# MotorController.net
KiCad netlist of a schematic drawn in EAGLE
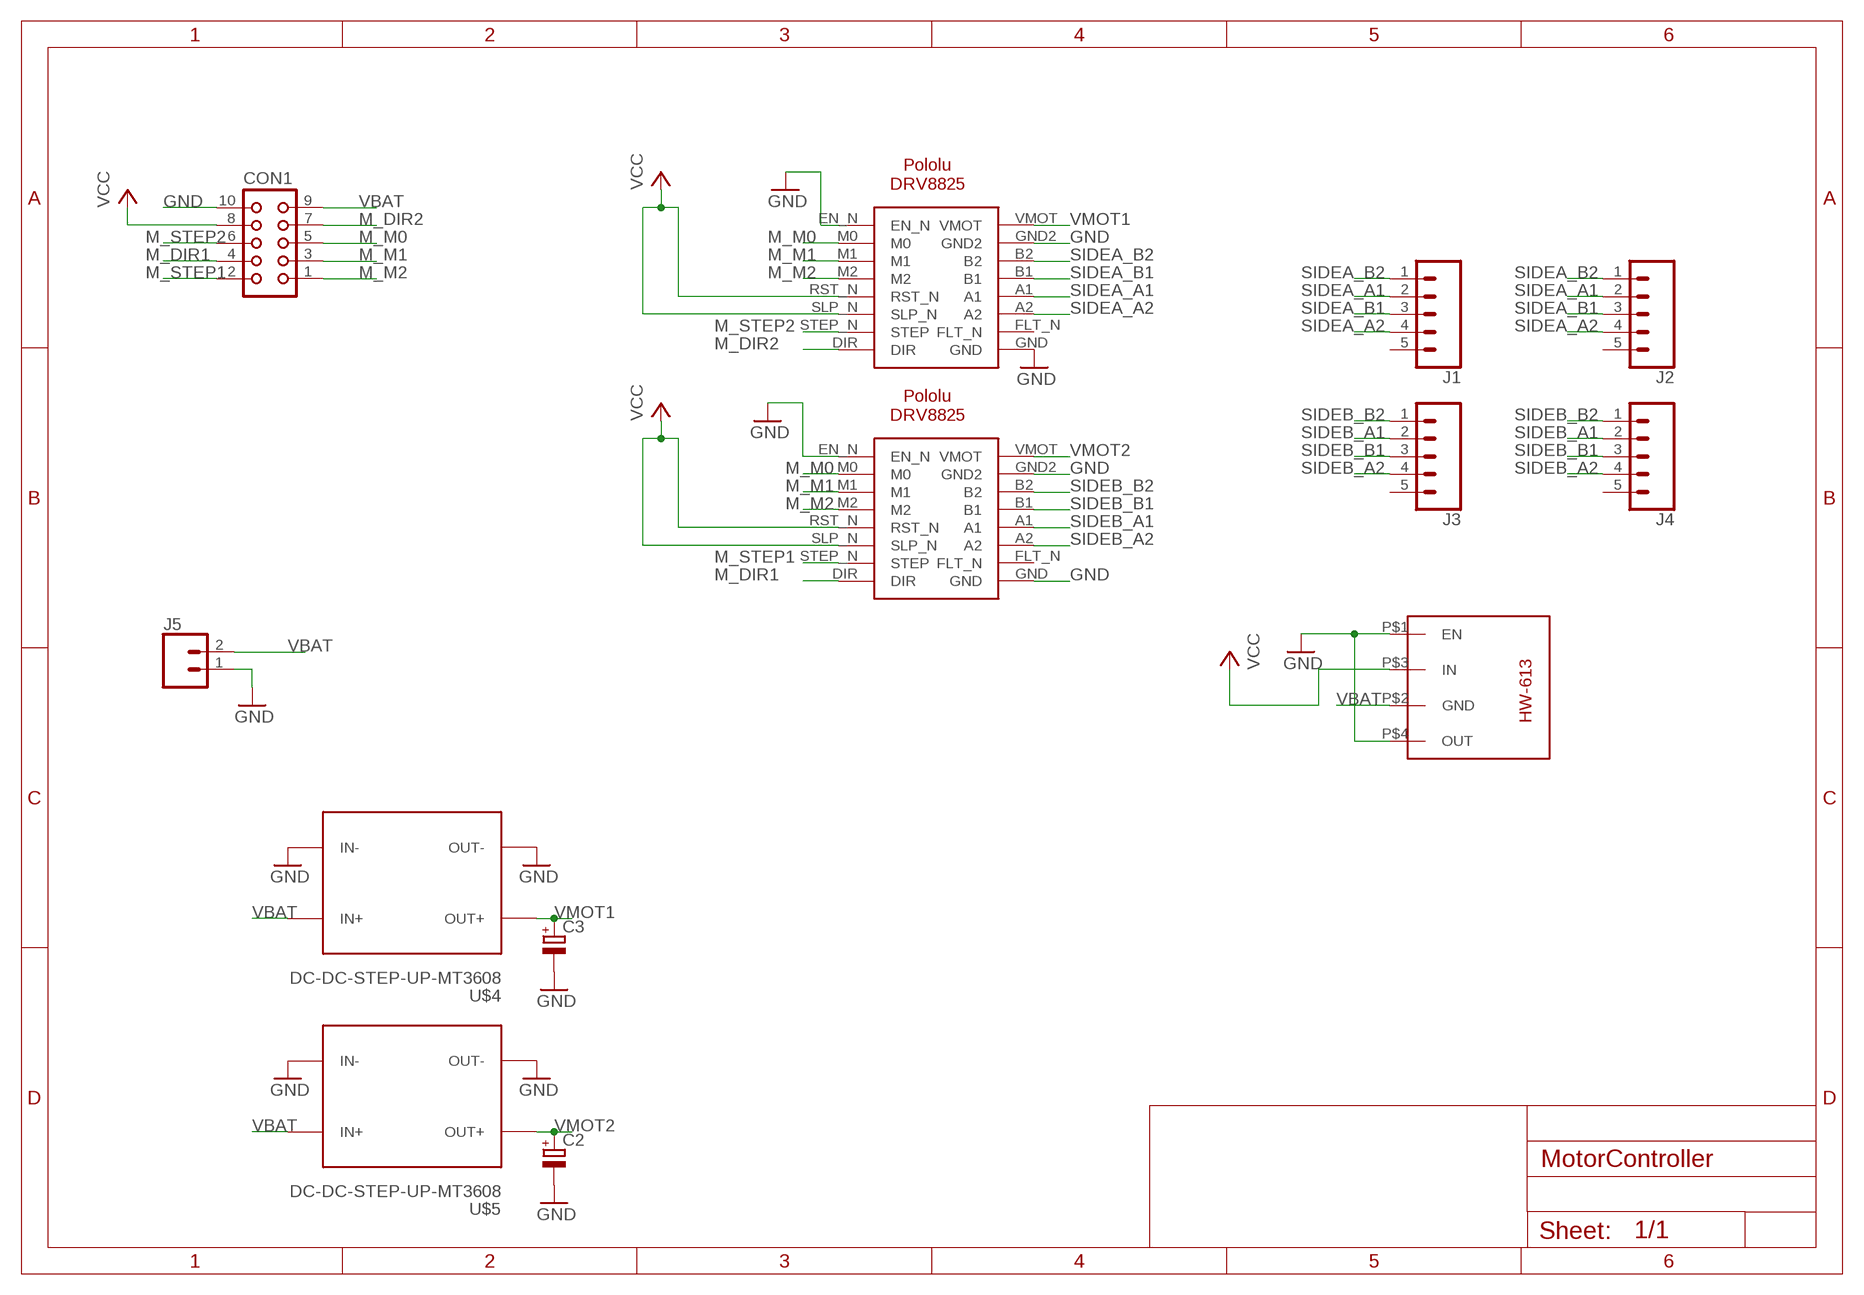
[diagram p0: schematic, sheet 1]

(export (version "E")
  (design (tool "Eeschema 10.0.6"))
  (components
    (comp (ref "C2")
      (value "CPOL-EUE3.5-10")
      (footprint "eagle-import:E3,5-10")
      (libsource (lib "eagle-import") (part "CPOL-EUE3.5-10"))
    )
    (comp (ref "C3")
      (value "CPOL-EUE3.5-10")
      (footprint "eagle-import:E3,5-10")
      (libsource (lib "eagle-import") (part "CPOL-EUE3.5-10"))
    )
    (comp (ref "CON1")
      (value "CON10")
      (footprint "eagle-import:CON10")
      (libsource (lib "eagle-import") (part "CON10"))
    )
    (comp (ref "J1")
      (value "CONN_05")
      (footprint "eagle-import:1X05")
      (libsource (lib "eagle-import") (part "CONN_05"))
    )
    (comp (ref "J2")
      (value "CONN_05")
      (footprint "eagle-import:1X05")
      (libsource (lib "eagle-import") (part "CONN_05"))
    )
    (comp (ref "J3")
      (value "CONN_05")
      (footprint "eagle-import:1X05")
      (libsource (lib "eagle-import") (part "CONN_05"))
    )
    (comp (ref "J4")
      (value "CONN_05")
      (footprint "eagle-import:1X05")
      (libsource (lib "eagle-import") (part "CONN_05"))
    )
    (comp (ref "J5")
      (value "CONN_025MM")
      (footprint "eagle-import:SCREWTERMINAL-5MM-2")
      (libsource (lib "eagle-import") (part "CONN_025MM"))
    )
    (comp (ref "U$1")
      (value "POLOLU-DRV8825")
      (footprint "eagle-import:POLOLU-DRV8825")
      (libsource (lib "eagle-import") (part "POLOLU-DRV8825"))
    )
    (comp (ref "U$2")
      (value "POLOLU-DRV8825")
      (footprint "eagle-import:POLOLU-DRV8825")
      (libsource (lib "eagle-import") (part "POLOLU-DRV8825"))
    )
    (comp (ref "U$4")
      (value "DC-DC-STEP-UP-MT3608")
      (footprint "eagle-import:DC-DC-STEP-UP-MT3608")
      (libsource (lib "eagle-import") (part "DC-DC-STEP-UP-MT3608"))
    )
    (comp (ref "U$5")
      (value "DC-DC-STEP-UP-MT3608")
      (footprint "eagle-import:DC-DC-STEP-UP-MT3608")
      (libsource (lib "eagle-import") (part "DC-DC-STEP-UP-MT3608"))
    )
    (comp (ref "U$6")
      (value "HW-613")
      (footprint "eagle-import:HW-613")
      (libsource (lib "eagle-import") (part "HW-613"))
    )
  )
  (nets
    (net (code "1") (name "/M_DIR1") (class "Default")
      (node (ref "CON1") (pin "4") (pinfunction "4_4") (pintype "passive"))
      (node (ref "U$2") (pin "DIR") (pinfunction "DIR_DIR") (pintype "bidirectional"))
    )
    (net (code "2") (name "/M_DIR2") (class "Default")
      (node (ref "CON1") (pin "7") (pinfunction "7_7") (pintype "passive"))
      (node (ref "U$1") (pin "DIR") (pinfunction "DIR_DIR") (pintype "bidirectional"))
    )
    (net (code "3") (name "/M_M0") (class "Default")
      (node (ref "CON1") (pin "5") (pinfunction "5_5") (pintype "passive"))
      (node (ref "U$1") (pin "M0") (pinfunction "M0_M0") (pintype "bidirectional"))
      (node (ref "U$2") (pin "M0") (pinfunction "M0_M0") (pintype "bidirectional"))
    )
    (net (code "4") (name "/M_M1") (class "Default")
      (node (ref "CON1") (pin "3") (pinfunction "3_3") (pintype "passive"))
      (node (ref "U$1") (pin "M1") (pinfunction "M1_M1") (pintype "bidirectional"))
      (node (ref "U$2") (pin "M1") (pinfunction "M1_M1") (pintype "bidirectional"))
    )
    (net (code "5") (name "/M_M2") (class "Default")
      (node (ref "CON1") (pin "1") (pinfunction "1_1") (pintype "passive"))
      (node (ref "U$1") (pin "M2") (pinfunction "M2_M2") (pintype "bidirectional"))
      (node (ref "U$2") (pin "M2") (pinfunction "M2_M2") (pintype "bidirectional"))
    )
    (net (code "6") (name "/M_STEP1") (class "Default")
      (node (ref "CON1") (pin "2") (pinfunction "2_2") (pintype "passive"))
      (node (ref "U$2") (pin "STEP_N") (pinfunction "STEP_STEP_N") (pintype "bidirectional"))
    )
    (net (code "7") (name "/M_STEP2") (class "Default")
      (node (ref "CON1") (pin "6") (pinfunction "6_6") (pintype "passive"))
      (node (ref "U$1") (pin "STEP_N") (pinfunction "STEP_STEP_N") (pintype "bidirectional"))
    )
    (net (code "8") (name "/SIDEA_A1") (class "Default")
      (node (ref "J1") (pin "2") (pinfunction "2_2") (pintype "passive"))
      (node (ref "J2") (pin "2") (pinfunction "2_2") (pintype "passive"))
      (node (ref "U$1") (pin "A1") (pinfunction "A1_A1") (pintype "bidirectional"))
    )
    (net (code "9") (name "/SIDEA_A2") (class "Default")
      (node (ref "J1") (pin "4") (pinfunction "4_4") (pintype "passive"))
      (node (ref "J2") (pin "4") (pinfunction "4_4") (pintype "passive"))
      (node (ref "U$1") (pin "A2") (pinfunction "A2_A2") (pintype "bidirectional"))
    )
    (net (code "10") (name "/SIDEA_B1") (class "Default")
      (node (ref "J1") (pin "3") (pinfunction "3_3") (pintype "passive"))
      (node (ref "J2") (pin "3") (pinfunction "3_3") (pintype "passive"))
      (node (ref "U$1") (pin "B1") (pinfunction "B1_B1") (pintype "bidirectional"))
    )
    (net (code "11") (name "/SIDEA_B2") (class "Default")
      (node (ref "J1") (pin "1") (pinfunction "1_1") (pintype "passive"))
      (node (ref "J2") (pin "1") (pinfunction "1_1") (pintype "passive"))
      (node (ref "U$1") (pin "B2") (pinfunction "B2_B2") (pintype "bidirectional"))
    )
    (net (code "12") (name "/SIDEB_A1") (class "Default")
      (node (ref "J3") (pin "2") (pinfunction "2_2") (pintype "passive"))
      (node (ref "J4") (pin "2") (pinfunction "2_2") (pintype "passive"))
      (node (ref "U$2") (pin "A1") (pinfunction "A1_A1") (pintype "bidirectional"))
    )
    (net (code "13") (name "/SIDEB_A2") (class "Default")
      (node (ref "J3") (pin "4") (pinfunction "4_4") (pintype "passive"))
      (node (ref "J4") (pin "4") (pinfunction "4_4") (pintype "passive"))
      (node (ref "U$2") (pin "A2") (pinfunction "A2_A2") (pintype "bidirectional"))
    )
    (net (code "14") (name "/SIDEB_B1") (class "Default")
      (node (ref "J3") (pin "3") (pinfunction "3_3") (pintype "passive"))
      (node (ref "J4") (pin "3") (pinfunction "3_3") (pintype "passive"))
      (node (ref "U$2") (pin "B1") (pinfunction "B1_B1") (pintype "bidirectional"))
    )
    (net (code "15") (name "/SIDEB_B2") (class "Default")
      (node (ref "J3") (pin "1") (pinfunction "1_1") (pintype "passive"))
      (node (ref "J4") (pin "1") (pinfunction "1_1") (pintype "passive"))
      (node (ref "U$2") (pin "B2") (pinfunction "B2_B2") (pintype "bidirectional"))
    )
    (net (code "16") (name "/VBAT") (class "Default")
      (node (ref "CON1") (pin "9") (pinfunction "9_9") (pintype "passive"))
      (node (ref "J5") (pin "2") (pinfunction "2_2") (pintype "passive"))
      (node (ref "U$4") (pin "IN+") (pinfunction "IN+_IN+") (pintype "bidirectional"))
      (node (ref "U$5") (pin "IN+") (pinfunction "IN+_IN+") (pintype "bidirectional"))
      (node (ref "U$6") (pin "P$2") (pinfunction "GND_P$2") (pintype "bidirectional"))
    )
    (net (code "17") (name "/VMOT1") (class "Default")
      (node (ref "C3") (pin "+") (pinfunction "+_+") (pintype "passive"))
      (node (ref "U$1") (pin "VMOT") (pinfunction "VMOT_VMOT") (pintype "bidirectional"))
      (node (ref "U$4") (pin "OUT+") (pinfunction "OUT+_OUT+") (pintype "bidirectional"))
    )
    (net (code "18") (name "/VMOT2") (class "Default")
      (node (ref "C2") (pin "+") (pinfunction "+_+") (pintype "passive"))
      (node (ref "U$2") (pin "VMOT") (pinfunction "VMOT_VMOT") (pintype "bidirectional"))
      (node (ref "U$5") (pin "OUT+") (pinfunction "OUT+_OUT+") (pintype "bidirectional"))
    )
    (net (code "19") (name "GND") (class "Default")
      (node (ref "C2") (pin "-") (pinfunction "-_-") (pintype "passive"))
      (node (ref "C3") (pin "-") (pinfunction "-_-") (pintype "passive"))
      (node (ref "CON1") (pin "10") (pinfunction "10_10") (pintype "passive"))
      (node (ref "J5") (pin "1") (pinfunction "1_1") (pintype "passive"))
      (node (ref "U$1") (pin "EN_N") (pinfunction "EN_N_EN_N") (pintype "bidirectional"))
      (node (ref "U$1") (pin "GND") (pinfunction "GND_GND") (pintype "bidirectional"))
      (node (ref "U$1") (pin "GND2") (pinfunction "GND2_GND2") (pintype "bidirectional"))
      (node (ref "U$2") (pin "EN_N") (pinfunction "EN_N_EN_N") (pintype "bidirectional"))
      (node (ref "U$2") (pin "GND") (pinfunction "GND_GND") (pintype "bidirectional"))
      (node (ref "U$2") (pin "GND2") (pinfunction "GND2_GND2") (pintype "bidirectional"))
      (node (ref "U$4") (pin "IN-") (pinfunction "IN-_IN-") (pintype "bidirectional"))
      (node (ref "U$4") (pin "OUT-") (pinfunction "OUT-_OUT-") (pintype "bidirectional"))
      (node (ref "U$5") (pin "IN-") (pinfunction "IN-_IN-") (pintype "bidirectional"))
      (node (ref "U$5") (pin "OUT-") (pinfunction "OUT-_OUT-") (pintype "bidirectional"))
      (node (ref "U$6") (pin "P$1") (pinfunction "EN_P$1") (pintype "bidirectional"))
      (node (ref "U$6") (pin "P$4") (pinfunction "OUT_P$4") (pintype "bidirectional"))
    )
    (net (code "20") (name "VCC") (class "Default")
      (node (ref "CON1") (pin "8") (pinfunction "8_8") (pintype "passive"))
      (node (ref "U$1") (pin "RST_N") (pinfunction "RST_N_RST_N") (pintype "bidirectional"))
      (node (ref "U$1") (pin "SLP_N") (pinfunction "SLP_N_SLP_N") (pintype "bidirectional"))
      (node (ref "U$2") (pin "RST_N") (pinfunction "RST_N_RST_N") (pintype "bidirectional"))
      (node (ref "U$2") (pin "SLP_N") (pinfunction "SLP_N_SLP_N") (pintype "bidirectional"))
      (node (ref "U$6") (pin "P$3") (pinfunction "IN_P$3") (pintype "bidirectional"))
    )
    (net (code "21") (name "unconnected-(J1-Pad5)") (class "Default")
      (node (ref "J1") (pin "5") (pinfunction "5_5") (pintype "passive"))
    )
    (net (code "22") (name "unconnected-(J2-Pad5)") (class "Default")
      (node (ref "J2") (pin "5") (pinfunction "5_5") (pintype "passive"))
    )
    (net (code "23") (name "unconnected-(J3-Pad5)") (class "Default")
      (node (ref "J3") (pin "5") (pinfunction "5_5") (pintype "passive"))
    )
    (net (code "24") (name "unconnected-(J4-Pad5)") (class "Default")
      (node (ref "J4") (pin "5") (pinfunction "5_5") (pintype "passive"))
    )
    (net (code "25") (name "unconnected-(U$1-PadFLT_N)") (class "Default")
      (node (ref "U$1") (pin "FLT_N") (pinfunction "FLT_N_FLT_N") (pintype "bidirectional"))
    )
    (net (code "26") (name "unconnected-(U$2-PadFLT_N)") (class "Default")
      (node (ref "U$2") (pin "FLT_N") (pinfunction "FLT_N_FLT_N") (pintype "bidirectional"))
    )
  )
)
